# BOC_CLK_ADJ.net
KiCad netlist of a schematic drawn in Altium Designer
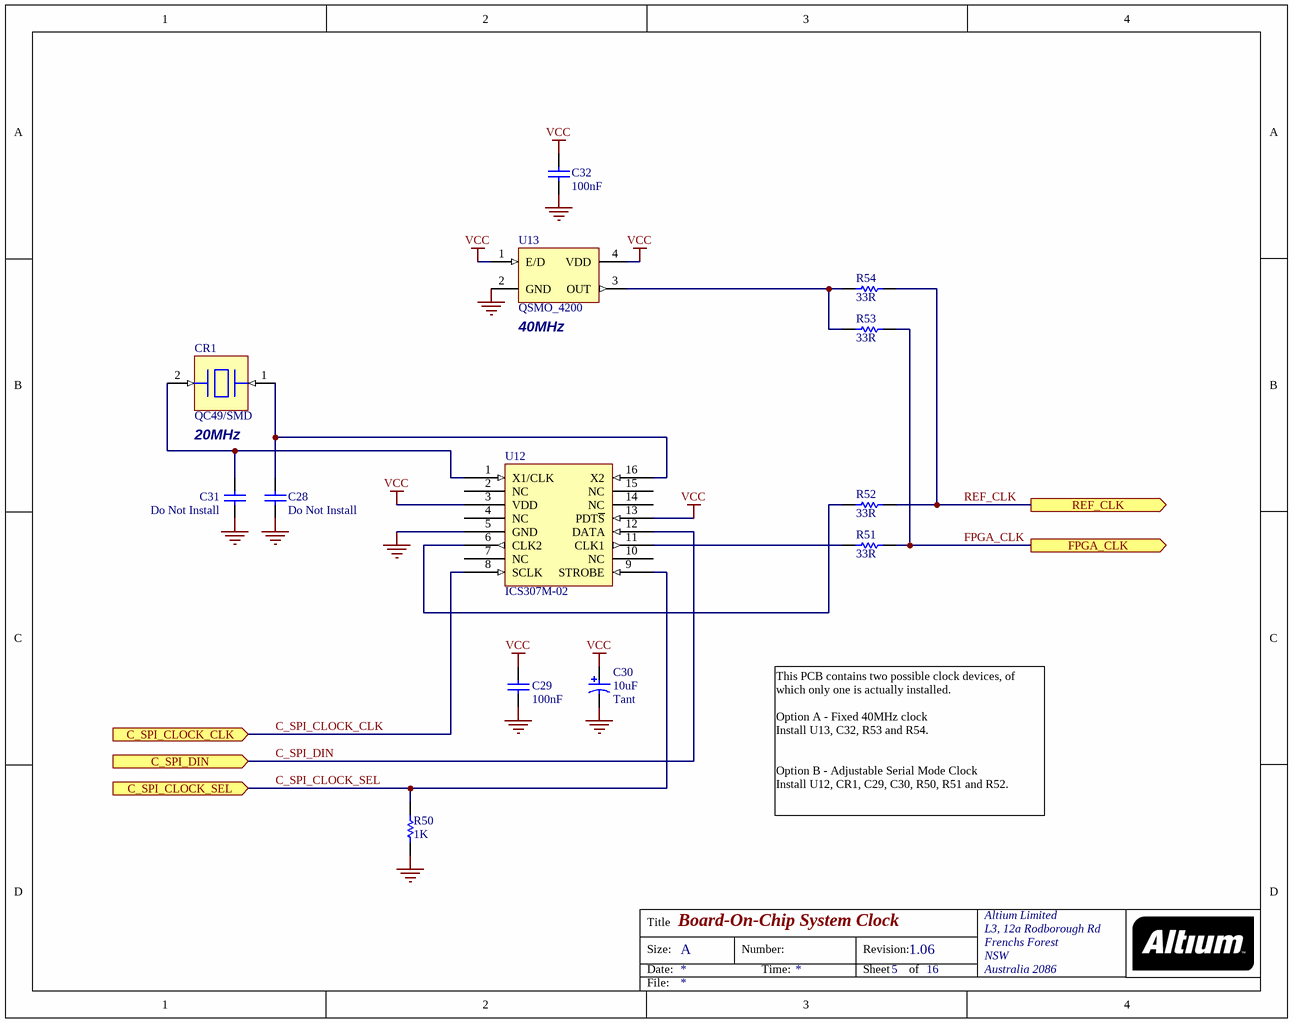
[diagram p0: BOC_CLK_ADJ.SchDoc]

(export (version "E")
  (design (tool "Eeschema 10.0.6"))
  (components
    (comp (ref "C28")
      (value "Do Not Install")
      (footprint "Altium Nanoboard Project:CC2012-0805")
      (description "Capacitor")
      (libsource (lib "Altium Nanoboard Project") (part "CAP"))
    )
    (comp (ref "C29")
      (value "100nF")
      (footprint "Altium Nanoboard Project:CC2012-0805")
      (description "Capacitor")
      (libsource (lib "Altium Nanoboard Project") (part "CAP"))
    )
    (comp (ref "C30")
      (value "10uF")
      (footprint "Altium Nanoboard Project:MCCT-B")
      (description "Polar Capacitor")
      (fields (field (name "CAPACITOR TYPE") "Tant"))
      (libsource (lib "Altium Nanoboard Project") (part "CAP_POLAR"))
    )
    (comp (ref "C31")
      (value "Do Not Install")
      (footprint "Altium Nanoboard Project:CC2012-0805")
      (description "Capacitor")
      (libsource (lib "Altium Nanoboard Project") (part "CAP"))
    )
    (comp (ref "C32")
      (value "100nF")
      (footprint "Altium Nanoboard Project:CC2012-0805")
      (description "Capacitor")
      (libsource (lib "Altium Nanoboard Project") (part "CAP"))
    )
    (comp (ref "CR1")
      (value "QC49/SMD")
      (footprint "Altium Nanoboard Project:QC49/SMD")
      (description "SMD Crystal 20MHz HY-Q")
      (libsource (lib "Altium Nanoboard Project") (part "QC49/SMD"))
    )
    (comp (ref "R50")
      (value "1K")
      (footprint "Altium Nanoboard Project:CC2012-0805")
      (description "Resistor")
      (libsource (lib "Altium Nanoboard Project") (part "RES"))
    )
    (comp (ref "R51")
      (value "33R")
      (footprint "Altium Nanoboard Project:CC2012-0805")
      (description "Resistor")
      (libsource (lib "Altium Nanoboard Project") (part "RES"))
    )
    (comp (ref "R52")
      (value "33R")
      (footprint "Altium Nanoboard Project:CC2012-0805")
      (description "Resistor")
      (libsource (lib "Altium Nanoboard Project") (part "RES"))
    )
    (comp (ref "R53")
      (value "33R")
      (footprint "Altium Nanoboard Project:CC2012-0805")
      (description "Resistor")
      (libsource (lib "Altium Nanoboard Project") (part "RES"))
    )
    (comp (ref "R54")
      (value "33R")
      (footprint "Altium Nanoboard Project:CC2012-0805")
      (description "Resistor")
      (libsource (lib "Altium Nanoboard Project") (part "RES"))
    )
    (comp (ref "U12")
      (value "ICS307M-02")
      (footprint "Altium Nanoboard Project:SO-G16")
      (description "Serial Programmable PLL Oscillator")
      (libsource (lib "Altium Nanoboard Project") (part "ICS307-02"))
    )
    (comp (ref "U13")
      (value "QSMO_4200")
      (footprint "Altium Nanoboard Project:QSMO_4200")
      (description "Surface Mount Crystal Oscillator")
      (libsource (lib "Altium Nanoboard Project") (part "QSMO_4200"))
    )
  )
  (nets
    (net (code "1") (name "/C_SPI_CLOCK_CLK") (class "Default")
      (node (ref "U12") (pin "8") (pinfunction "SCLK_8") (pintype "input"))
    )
    (net (code "2") (name "/C_SPI_CLOCK_SEL") (class "Default")
      (node (ref "R50") (pin "1") (pinfunction "1_1") (pintype "passive"))
      (node (ref "U12") (pin "9") (pinfunction "STROBE_9") (pintype "input"))
    )
    (net (code "3") (name "/C_SPI_DIN") (class "Default")
      (node (ref "U12") (pin "12") (pinfunction "DATA_12") (pintype "input"))
    )
    (net (code "4") (name "/FPGA_CLK") (class "Default")
      (node (ref "R51") (pin "2") (pinfunction "2_2") (pintype "passive"))
      (node (ref "R53") (pin "2") (pinfunction "2_2") (pintype "passive"))
    )
    (net (code "5") (name "/REF_CLK") (class "Default")
      (node (ref "R52") (pin "2") (pinfunction "2_2") (pintype "passive"))
      (node (ref "R54") (pin "2") (pinfunction "2_2") (pintype "passive"))
    )
    (net (code "6") (name "GND") (class "Default")
      (node (ref "C28") (pin "2") (pinfunction "2_2") (pintype "passive"))
      (node (ref "C29") (pin "2") (pinfunction "2_2") (pintype "passive"))
      (node (ref "C30") (pin "2") (pinfunction "2_2") (pintype "passive"))
      (node (ref "C31") (pin "2") (pinfunction "2_2") (pintype "passive"))
      (node (ref "C32") (pin "2") (pinfunction "2_2") (pintype "passive"))
      (node (ref "R50") (pin "2") (pinfunction "2_2") (pintype "passive"))
      (node (ref "U12") (pin "5") (pinfunction "GND_5") (pintype "power_in"))
      (node (ref "U13") (pin "2") (pinfunction "GND_2") (pintype "power_in"))
    )
    (net (code "7") (name "Net-(U12-CLK1)") (class "Default")
      (node (ref "R51") (pin "1") (pinfunction "1_1") (pintype "passive"))
      (node (ref "U12") (pin "11") (pinfunction "CLK1_11") (pintype "output"))
    )
    (net (code "8") (name "Net-(U12-CLK2)") (class "Default")
      (node (ref "R52") (pin "1") (pinfunction "1_1") (pintype "passive"))
      (node (ref "U12") (pin "6") (pinfunction "CLK2_6") (pintype "output"))
    )
    (net (code "9") (name "Net-(U12-X1{slash}CLK)") (class "Default")
      (node (ref "C31") (pin "1") (pinfunction "1_1") (pintype "passive"))
      (node (ref "CR1") (pin "2") (pinfunction "2_2") (pintype "input"))
      (node (ref "U12") (pin "1") (pinfunction "X1/CLK_1") (pintype "input"))
    )
    (net (code "10") (name "Net-(U12-X2)") (class "Default")
      (node (ref "C28") (pin "1") (pinfunction "1_1") (pintype "passive"))
      (node (ref "CR1") (pin "1") (pinfunction "1_1") (pintype "input"))
      (node (ref "U12") (pin "16") (pinfunction "X2_16") (pintype "input"))
    )
    (net (code "11") (name "Net-(U13-OUT)") (class "Default")
      (node (ref "R53") (pin "1") (pinfunction "1_1") (pintype "passive"))
      (node (ref "R54") (pin "1") (pinfunction "1_1") (pintype "passive"))
      (node (ref "U13") (pin "3") (pinfunction "OUT_3") (pintype "output"))
    )
    (net (code "12") (name "VCC") (class "Default")
      (node (ref "C29") (pin "1") (pinfunction "1_1") (pintype "passive"))
      (node (ref "C30") (pin "1") (pinfunction "1_1") (pintype "passive"))
      (node (ref "C32") (pin "1") (pinfunction "1_1") (pintype "passive"))
      (node (ref "U12") (pin "13") (pinfunction "PDT~{S}_13") (pintype "input"))
      (node (ref "U12") (pin "3") (pinfunction "VDD_3") (pintype "power_in"))
      (node (ref "U13") (pin "1") (pinfunction "E/D_1") (pintype "input"))
      (node (ref "U13") (pin "4") (pinfunction "VDD_4") (pintype "power_in"))
    )
    (net (code "13") (name "unconnected-(U12-NC-Pad2)") (class "Default")
      (node (ref "U12") (pin "2") (pinfunction "NC_2") (pintype "passive"))
    )
    (net (code "14") (name "unconnected-(U12-NC-Pad4)") (class "Default")
      (node (ref "U12") (pin "4") (pinfunction "NC_4") (pintype "passive"))
    )
    (net (code "15") (name "unconnected-(U12-NC-Pad7)") (class "Default")
      (node (ref "U12") (pin "7") (pinfunction "NC_7") (pintype "passive"))
    )
    (net (code "16") (name "unconnected-(U12-NC-Pad10)") (class "Default")
      (node (ref "U12") (pin "10") (pinfunction "NC_10") (pintype "passive"))
    )
    (net (code "17") (name "unconnected-(U12-NC-Pad14)") (class "Default")
      (node (ref "U12") (pin "14") (pinfunction "NC_14") (pintype "passive"))
    )
    (net (code "18") (name "unconnected-(U12-NC-Pad15)") (class "Default")
      (node (ref "U12") (pin "15") (pinfunction "NC_15") (pintype "passive"))
    )
  )
)
